# dozer_mover.net
KiCad netlist of a schematic drawn in EAGLE
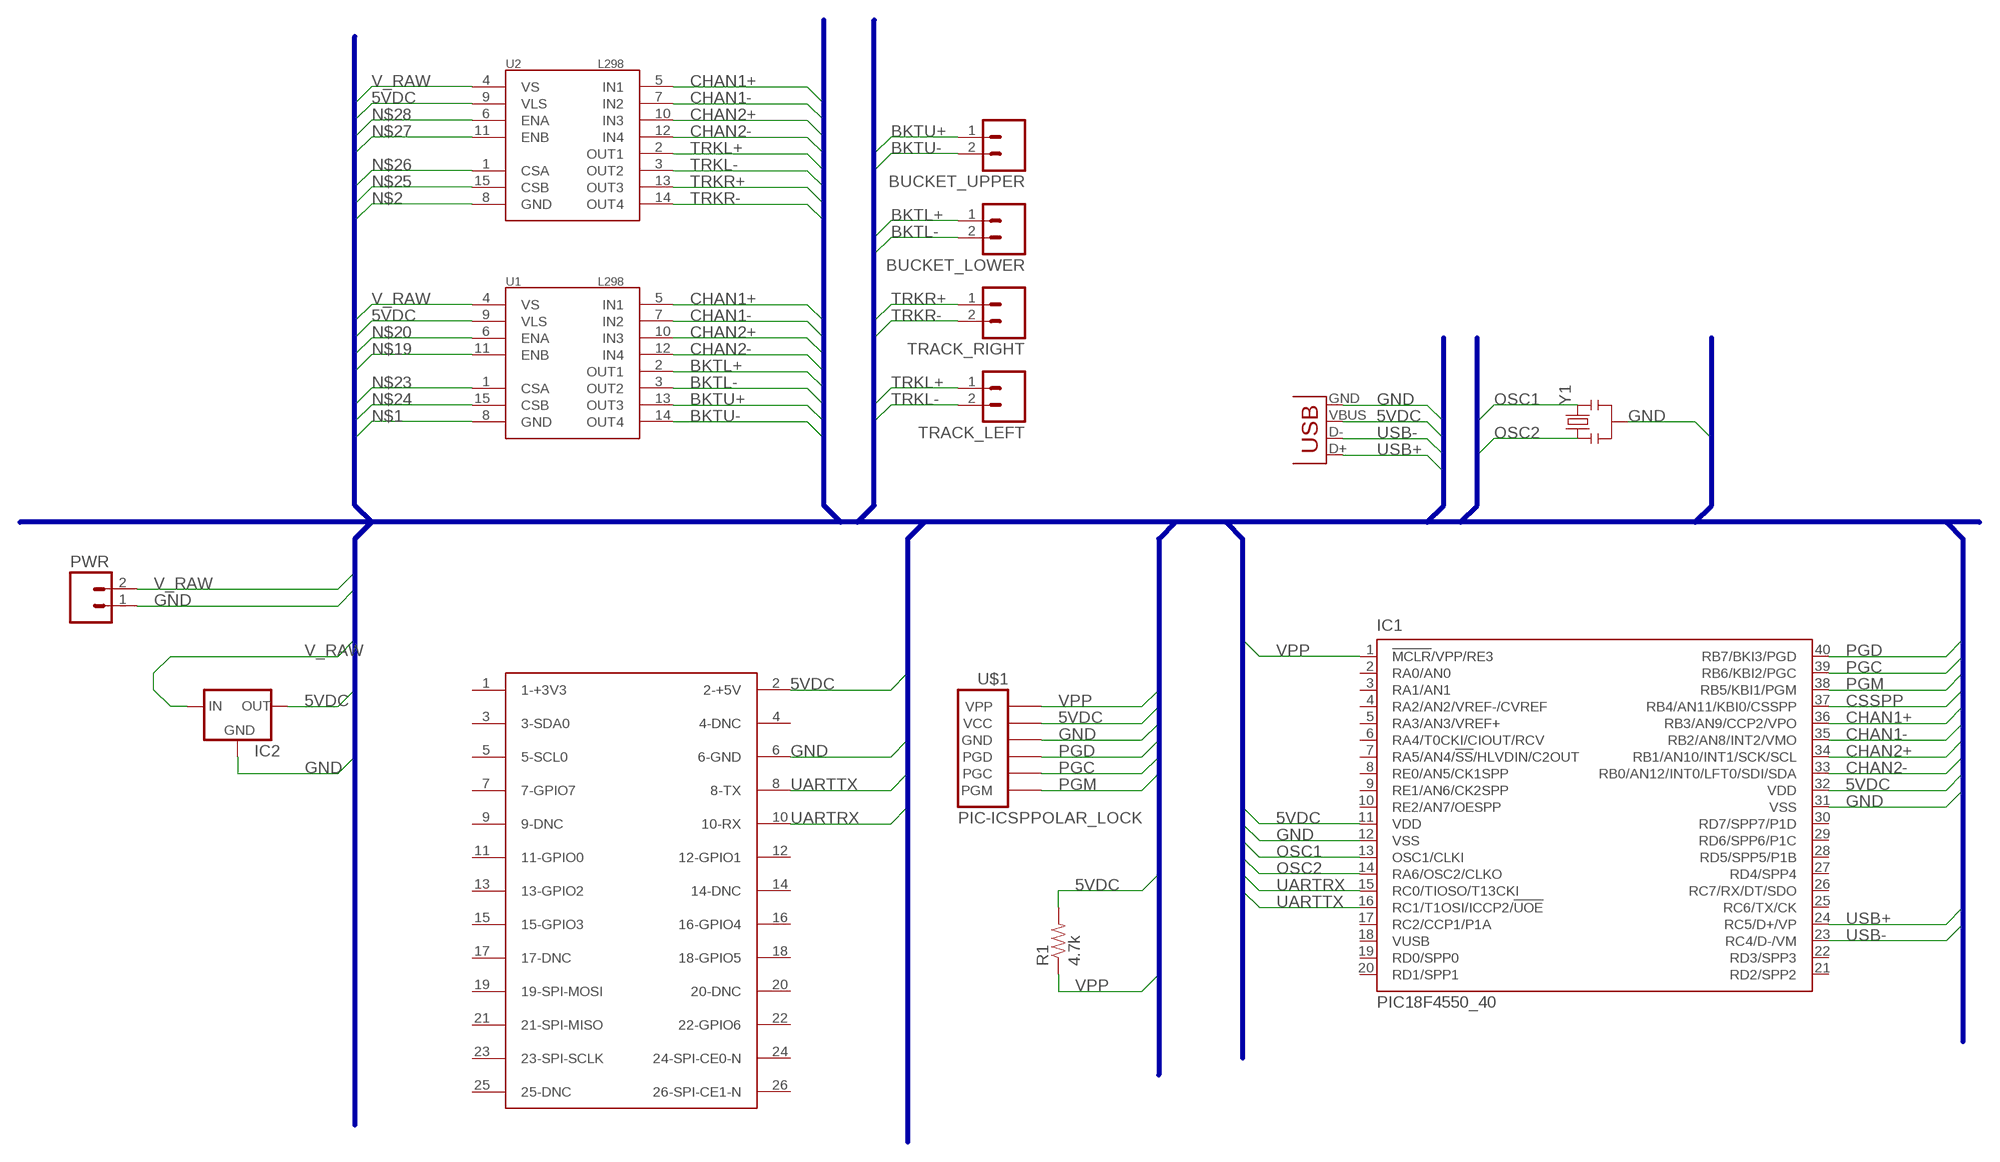
[diagram p0: schematic, sheet 1]

(export (version "E")
  (design (tool "Eeschema 10.0.6"))
  (components
    (comp (ref "BUCKET_LOWER")
      (value "M02JST-PTH-2")
      (footprint "eagle-import:JST-2-PTH")
      (libsource (lib "eagle-import") (part "M02JST-PTH-2"))
    )
    (comp (ref "BUCKET_UPPER")
      (value "M02JST-PTH-2")
      (footprint "eagle-import:JST-2-PTH")
      (libsource (lib "eagle-import") (part "M02JST-PTH-2"))
    )
    (comp (ref "IC1")
      (value "PIC18F4550_40")
      (footprint "eagle-import:DIL40")
      (fields (field (name "MF") "MICROCHIP") (field (name "MPN") "PIC18F4550-I/P"))
      (libsource (lib "eagle-import") (part "PIC18F4_40550"))
    )
    (comp (ref "IC2")
      (value "V_REG_78XXSINK")
      (footprint "eagle-import:TO220-IGO")
      (libsource (lib "eagle-import") (part "V_REG_78XXSINK"))
    )
    (comp (ref "J1")
      (value "RASPBERRY-PI")
      (footprint "eagle-import:RASPBERRY-PI")
      (libsource (lib "eagle-import") (part "RASPBERRY-PI"))
    )
    (comp (ref "JP1")
      (value "USB-MB-H")
      (footprint "eagle-import:USB-MB-H")
      (libsource (lib "eagle-import") (part "USB-MB-H"))
    )
    (comp (ref "PWR")
      (value "M02JST-PTH-2")
      (footprint "eagle-import:JST-2-PTH")
      (libsource (lib "eagle-import") (part "M02JST-PTH-2"))
    )
    (comp (ref "R1")
      (value "4.7k")
      (footprint "eagle-import:AXIAL-0.4")
      (libsource (lib "eagle-import") (part "RESISTORPTH-1/4W"))
    )
    (comp (ref "TRACK_LEFT")
      (value "M02JST-PTH-2")
      (footprint "eagle-import:JST-2-PTH")
      (libsource (lib "eagle-import") (part "M02JST-PTH-2"))
    )
    (comp (ref "TRACK_RIGHT")
      (value "M02JST-PTH-2")
      (footprint "eagle-import:JST-2-PTH")
      (libsource (lib "eagle-import") (part "M02JST-PTH-2"))
    )
    (comp (ref "U$1")
      (value "PIC-ICSPPOLAR_LOCK")
      (footprint "eagle-import:MOLEX-1X6_LOCK")
      (libsource (lib "eagle-import") (part "PIC-ICSPPOLAR_LOCK"))
    )
    (comp (ref "U1")
      (value "L298")
      (footprint "eagle-import:MULTIWATT15")
      (libsource (lib "eagle-import") (part "L298"))
    )
    (comp (ref "U2")
      (value "L298")
      (footprint "eagle-import:MULTIWATT15")
      (libsource (lib "eagle-import") (part "L298"))
    )
    (comp (ref "Y1")
      (value "RESONATORPTH")
      (footprint "eagle-import:RESONATOR-PTH")
      (libsource (lib "eagle-import") (part "RESONATORPTH"))
    )
  )
  (nets
    (net (code "1") (name "/5VDC") (class "Default")
      (node (ref "IC1") (pin "11") (pinfunction "VDD_11") (pintype "power_in"))
      (node (ref "IC1") (pin "32") (pinfunction "VDD_32") (pintype "power_in"))
      (node (ref "IC2") (pin "OUT") (pinfunction "OUT_OUT") (pintype "output"))
      (node (ref "J1") (pin "2") (pinfunction "2-+5V_2") (pintype "bidirectional"))
      (node (ref "JP1") (pin "VBUS") (pinfunction "VBUS_VBUS") (pintype "bidirectional"))
      (node (ref "R1") (pin "P$2") (pinfunction "2_P$2") (pintype "passive"))
      (node (ref "U$1") (pin "5") (pinfunction "VCC_5") (pintype "bidirectional"))
      (node (ref "U1") (pin "9") (pinfunction "VLS_9") (pintype "bidirectional"))
      (node (ref "U2") (pin "9") (pinfunction "VLS_9") (pintype "bidirectional"))
    )
    (net (code "2") (name "/BKTL+") (class "Default")
      (node (ref "BUCKET_LOWER") (pin "1") (pinfunction "1_1") (pintype "passive"))
      (node (ref "U1") (pin "2") (pinfunction "OUT1_2") (pintype "bidirectional"))
    )
    (net (code "3") (name "/BKTL-") (class "Default")
      (node (ref "BUCKET_LOWER") (pin "2") (pinfunction "2_2") (pintype "passive"))
      (node (ref "U1") (pin "3") (pinfunction "OUT2_3") (pintype "bidirectional"))
    )
    (net (code "4") (name "/BKTU+") (class "Default")
      (node (ref "BUCKET_UPPER") (pin "1") (pinfunction "1_1") (pintype "passive"))
      (node (ref "U1") (pin "13") (pinfunction "OUT3_13") (pintype "bidirectional"))
    )
    (net (code "5") (name "/BKTU-") (class "Default")
      (node (ref "BUCKET_UPPER") (pin "2") (pinfunction "2_2") (pintype "passive"))
      (node (ref "U1") (pin "14") (pinfunction "OUT4_14") (pintype "bidirectional"))
    )
    (net (code "6") (name "/CHAN1+") (class "Default")
      (node (ref "IC1") (pin "36") (pinfunction "RB3/AN9/CCP2/VPO_36") (pintype "bidirectional"))
      (node (ref "U1") (pin "5") (pinfunction "IN1_5") (pintype "bidirectional"))
      (node (ref "U2") (pin "5") (pinfunction "IN1_5") (pintype "bidirectional"))
    )
    (net (code "7") (name "/CHAN1-") (class "Default")
      (node (ref "IC1") (pin "35") (pinfunction "RB2/AN8/INT2/VMO_35") (pintype "bidirectional"))
      (node (ref "U1") (pin "7") (pinfunction "IN2_7") (pintype "bidirectional"))
      (node (ref "U2") (pin "7") (pinfunction "IN2_7") (pintype "bidirectional"))
    )
    (net (code "8") (name "/CHAN2+") (class "Default")
      (node (ref "IC1") (pin "34") (pinfunction "RB1/AN10/INT1/SCK/SCL_34") (pintype "bidirectional"))
      (node (ref "U1") (pin "10") (pinfunction "IN3_10") (pintype "bidirectional"))
      (node (ref "U2") (pin "10") (pinfunction "IN3_10") (pintype "bidirectional"))
    )
    (net (code "9") (name "/CHAN2-") (class "Default")
      (node (ref "IC1") (pin "33") (pinfunction "RB0/AN12/INT0/LFT0/SDI/SDA_33") (pintype "bidirectional"))
      (node (ref "U1") (pin "12") (pinfunction "IN4_12") (pintype "bidirectional"))
      (node (ref "U2") (pin "12") (pinfunction "IN4_12") (pintype "bidirectional"))
    )
    (net (code "10") (name "/CSSPP") (class "Default")
      (node (ref "IC1") (pin "37") (pinfunction "RB4/AN11/KBI0/CSSPP_37") (pintype "bidirectional"))
    )
    (net (code "11") (name "/GND") (class "Default")
      (node (ref "IC1") (pin "12") (pinfunction "VSS_12") (pintype "power_in"))
      (node (ref "IC1") (pin "31") (pinfunction "VSS_31") (pintype "power_in"))
      (node (ref "IC2") (pin "GND") (pinfunction "GND_GND") (pintype "input"))
      (node (ref "J1") (pin "6") (pinfunction "6-GND_6") (pintype "bidirectional"))
      (node (ref "JP1") (pin "GND") (pinfunction "GND_GND") (pintype "bidirectional"))
      (node (ref "PWR") (pin "1") (pinfunction "1_1") (pintype "passive"))
      (node (ref "U$1") (pin "4") (pinfunction "GND_4") (pintype "bidirectional"))
      (node (ref "Y1") (pin "2") (pinfunction "2_2") (pintype "passive"))
    )
    (net (code "12") (name "/N$1") (class "Default")
      (node (ref "U1") (pin "8") (pinfunction "GND_8") (pintype "bidirectional"))
    )
    (net (code "13") (name "/N$2") (class "Default")
      (node (ref "U2") (pin "8") (pinfunction "GND_8") (pintype "bidirectional"))
    )
    (net (code "14") (name "/N$19") (class "Default")
      (node (ref "U1") (pin "11") (pinfunction "ENB_11") (pintype "bidirectional"))
    )
    (net (code "15") (name "/N$20") (class "Default")
      (node (ref "U1") (pin "6") (pinfunction "ENA_6") (pintype "bidirectional"))
    )
    (net (code "16") (name "/N$23") (class "Default")
      (node (ref "U1") (pin "1") (pinfunction "CSA_1") (pintype "bidirectional"))
    )
    (net (code "17") (name "/N$24") (class "Default")
      (node (ref "U1") (pin "15") (pinfunction "CSB_15") (pintype "bidirectional"))
    )
    (net (code "18") (name "/N$25") (class "Default")
      (node (ref "U2") (pin "15") (pinfunction "CSB_15") (pintype "bidirectional"))
    )
    (net (code "19") (name "/N$26") (class "Default")
      (node (ref "U2") (pin "1") (pinfunction "CSA_1") (pintype "bidirectional"))
    )
    (net (code "20") (name "/N$27") (class "Default")
      (node (ref "U2") (pin "11") (pinfunction "ENB_11") (pintype "bidirectional"))
    )
    (net (code "21") (name "/N$28") (class "Default")
      (node (ref "U2") (pin "6") (pinfunction "ENA_6") (pintype "bidirectional"))
    )
    (net (code "22") (name "/OSC1") (class "Default")
      (node (ref "IC1") (pin "13") (pinfunction "OSC1/CLKI_13") (pintype "input"))
      (node (ref "Y1") (pin "3") (pinfunction "3_3") (pintype "passive"))
    )
    (net (code "23") (name "/OSC2") (class "Default")
      (node (ref "IC1") (pin "14") (pinfunction "RA6/OSC2/CLKO_14") (pintype "output"))
      (node (ref "Y1") (pin "1") (pinfunction "1_1") (pintype "passive"))
    )
    (net (code "24") (name "/PGC") (class "Default")
      (node (ref "IC1") (pin "39") (pinfunction "RB6/KBI2/PGC_39") (pintype "bidirectional"))
      (node (ref "U$1") (pin "2") (pinfunction "PGC_2") (pintype "bidirectional"))
    )
    (net (code "25") (name "/PGD") (class "Default")
      (node (ref "IC1") (pin "40") (pinfunction "RB7/BKI3/PGD_40") (pintype "bidirectional"))
      (node (ref "U$1") (pin "3") (pinfunction "PGD_3") (pintype "bidirectional"))
    )
    (net (code "26") (name "/PGM") (class "Default")
      (node (ref "IC1") (pin "38") (pinfunction "RB5/KBI1/PGM_38") (pintype "bidirectional"))
      (node (ref "U$1") (pin "1") (pinfunction "PGM_1") (pintype "bidirectional"))
    )
    (net (code "27") (name "/TRKL+") (class "Default")
      (node (ref "TRACK_LEFT") (pin "1") (pinfunction "1_1") (pintype "passive"))
      (node (ref "U2") (pin "2") (pinfunction "OUT1_2") (pintype "bidirectional"))
    )
    (net (code "28") (name "/TRKL-") (class "Default")
      (node (ref "TRACK_LEFT") (pin "2") (pinfunction "2_2") (pintype "passive"))
      (node (ref "U2") (pin "3") (pinfunction "OUT2_3") (pintype "bidirectional"))
    )
    (net (code "29") (name "/TRKR+") (class "Default")
      (node (ref "TRACK_RIGHT") (pin "1") (pinfunction "1_1") (pintype "passive"))
      (node (ref "U2") (pin "13") (pinfunction "OUT3_13") (pintype "bidirectional"))
    )
    (net (code "30") (name "/TRKR-") (class "Default")
      (node (ref "TRACK_RIGHT") (pin "2") (pinfunction "2_2") (pintype "passive"))
      (node (ref "U2") (pin "14") (pinfunction "OUT4_14") (pintype "bidirectional"))
    )
    (net (code "31") (name "/UARTRX") (class "Default")
      (node (ref "IC1") (pin "15") (pinfunction "RC0/TIOSO/T13CKI_15") (pintype "bidirectional"))
      (node (ref "J1") (pin "10") (pinfunction "10-RX_10") (pintype "bidirectional"))
    )
    (net (code "32") (name "/UARTTX") (class "Default")
      (node (ref "IC1") (pin "16") (pinfunction "RC1/T1OSI/ICCP2/~{UOE}_16") (pintype "bidirectional"))
      (node (ref "J1") (pin "8") (pinfunction "8-TX_8") (pintype "bidirectional"))
    )
    (net (code "33") (name "/USB+") (class "Default")
      (node (ref "IC1") (pin "24") (pinfunction "RC5/D+/VP_24") (pintype "bidirectional"))
      (node (ref "JP1") (pin "D+") (pinfunction "D+_D+") (pintype "bidirectional"))
    )
    (net (code "34") (name "/USB-") (class "Default")
      (node (ref "IC1") (pin "23") (pinfunction "RC4/D-/VM_23") (pintype "bidirectional"))
      (node (ref "JP1") (pin "D-") (pinfunction "D-_D-") (pintype "bidirectional"))
    )
    (net (code "35") (name "/VPP") (class "Default")
      (node (ref "IC1") (pin "1") (pinfunction "~{MCLR}/VPP/RE3_1") (pintype "input"))
      (node (ref "R1") (pin "P$1") (pinfunction "1_P$1") (pintype "passive"))
      (node (ref "U$1") (pin "6") (pinfunction "VPP_6") (pintype "bidirectional"))
    )
    (net (code "36") (name "/V_RAW") (class "Default")
      (node (ref "IC2") (pin "IN") (pinfunction "IN_IN") (pintype "input"))
      (node (ref "PWR") (pin "2") (pinfunction "2_2") (pintype "passive"))
      (node (ref "U1") (pin "4") (pinfunction "VS_4") (pintype "bidirectional"))
      (node (ref "U2") (pin "4") (pinfunction "VS_4") (pintype "bidirectional"))
    )
    (net (code "37") (name "unconnected-(IC1-RA0{slash}AN0-Pad2)") (class "Default")
      (node (ref "IC1") (pin "2") (pinfunction "RA0/AN0_2") (pintype "bidirectional"))
    )
    (net (code "38") (name "unconnected-(IC1-RA1{slash}AN1-Pad3)") (class "Default")
      (node (ref "IC1") (pin "3") (pinfunction "RA1/AN1_3") (pintype "bidirectional"))
    )
    (net (code "39") (name "unconnected-(IC1-RA2{slash}AN2{slash}VREF-{slash}CVREF-Pad4)") (class "Default")
      (node (ref "IC1") (pin "4") (pinfunction "RA2/AN2/VREF-/CVREF_4") (pintype "bidirectional"))
    )
    (net (code "40") (name "unconnected-(IC1-RA3{slash}AN3{slash}VREF+-Pad5)") (class "Default")
      (node (ref "IC1") (pin "5") (pinfunction "RA3/AN3/VREF+_5") (pintype "bidirectional"))
    )
    (net (code "41") (name "unconnected-(IC1-RA4{slash}T0CKI{slash}CIOUT{slash}RCV-Pad6)") (class "Default")
      (node (ref "IC1") (pin "6") (pinfunction "RA4/T0CKI/CIOUT/RCV_6") (pintype "bidirectional"))
    )
    (net (code "42") (name "unconnected-(IC1-RA5{slash}AN4{slash}~{SS}{slash}HLVDIN{slash}C2OUT-Pad7)") (class "Default")
      (node (ref "IC1") (pin "7") (pinfunction "RA5/AN4/~{SS}/HLVDIN/C2OUT_7") (pintype "bidirectional"))
    )
    (net (code "43") (name "unconnected-(IC1-RC2{slash}CCP1{slash}P1A-Pad17)") (class "Default")
      (node (ref "IC1") (pin "17") (pinfunction "RC2/CCP1/P1A_17") (pintype "bidirectional"))
    )
    (net (code "44") (name "unconnected-(IC1-RC6{slash}TX{slash}CK-Pad25)") (class "Default")
      (node (ref "IC1") (pin "25") (pinfunction "RC6/TX/CK_25") (pintype "bidirectional"))
    )
    (net (code "45") (name "unconnected-(IC1-RC7{slash}RX{slash}DT{slash}SDO-Pad26)") (class "Default")
      (node (ref "IC1") (pin "26") (pinfunction "RC7/RX/DT/SDO_26") (pintype "bidirectional"))
    )
    (net (code "46") (name "unconnected-(IC1-RD0{slash}SPP0-Pad19)") (class "Default")
      (node (ref "IC1") (pin "19") (pinfunction "RD0/SPP0_19") (pintype "bidirectional"))
    )
    (net (code "47") (name "unconnected-(IC1-RD1{slash}SPP1-Pad20)") (class "Default")
      (node (ref "IC1") (pin "20") (pinfunction "RD1/SPP1_20") (pintype "bidirectional"))
    )
    (net (code "48") (name "unconnected-(IC1-RD2{slash}SPP2-Pad21)") (class "Default")
      (node (ref "IC1") (pin "21") (pinfunction "RD2/SPP2_21") (pintype "bidirectional"))
    )
    (net (code "49") (name "unconnected-(IC1-RD3{slash}SPP3-Pad22)") (class "Default")
      (node (ref "IC1") (pin "22") (pinfunction "RD3/SPP3_22") (pintype "bidirectional"))
    )
    (net (code "50") (name "unconnected-(IC1-RD4{slash}SPP4-Pad27)") (class "Default")
      (node (ref "IC1") (pin "27") (pinfunction "RD4/SPP4_27") (pintype "bidirectional"))
    )
    (net (code "51") (name "unconnected-(IC1-RD5{slash}SPP5{slash}P1B-Pad28)") (class "Default")
      (node (ref "IC1") (pin "28") (pinfunction "RD5/SPP5/P1B_28") (pintype "bidirectional"))
    )
    (net (code "52") (name "unconnected-(IC1-RD6{slash}SPP6{slash}P1C-Pad29)") (class "Default")
      (node (ref "IC1") (pin "29") (pinfunction "RD6/SPP6/P1C_29") (pintype "bidirectional"))
    )
    (net (code "53") (name "unconnected-(IC1-RD7{slash}SPP7{slash}P1D-Pad30)") (class "Default")
      (node (ref "IC1") (pin "30") (pinfunction "RD7/SPP7/P1D_30") (pintype "bidirectional"))
    )
    (net (code "54") (name "unconnected-(IC1-RE0{slash}AN5{slash}CK1SPP-Pad8)") (class "Default")
      (node (ref "IC1") (pin "8") (pinfunction "RE0/AN5/CK1SPP_8") (pintype "bidirectional"))
    )
    (net (code "55") (name "unconnected-(IC1-RE1{slash}AN6{slash}CK2SPP-Pad9)") (class "Default")
      (node (ref "IC1") (pin "9") (pinfunction "RE1/AN6/CK2SPP_9") (pintype "bidirectional"))
    )
    (net (code "56") (name "unconnected-(IC1-RE2{slash}AN7{slash}OESPP-Pad10)") (class "Default")
      (node (ref "IC1") (pin "10") (pinfunction "RE2/AN7/OESPP_10") (pintype "bidirectional"))
    )
    (net (code "57") (name "unconnected-(IC1-VUSB-Pad18)") (class "Default")
      (node (ref "IC1") (pin "18") (pinfunction "VUSB_18") (pintype "bidirectional"))
    )
    (net (code "58") (name "unconnected-(J1-1-+3V3-Pad1)") (class "Default")
      (node (ref "J1") (pin "1") (pinfunction "1-+3V3_1") (pintype "bidirectional"))
    )
    (net (code "59") (name "unconnected-(J1-3-SDA0-Pad3)") (class "Default")
      (node (ref "J1") (pin "3") (pinfunction "3-SDA0_3") (pintype "bidirectional"))
    )
    (net (code "60") (name "unconnected-(J1-4-DNC-Pad4)") (class "Default")
      (node (ref "J1") (pin "4") (pinfunction "4-DNC_4") (pintype "bidirectional"))
    )
    (net (code "61") (name "unconnected-(J1-5-SCL0-Pad5)") (class "Default")
      (node (ref "J1") (pin "5") (pinfunction "5-SCL0_5") (pintype "bidirectional"))
    )
    (net (code "62") (name "unconnected-(J1-7-GPIO7-Pad7)") (class "Default")
      (node (ref "J1") (pin "7") (pinfunction "7-GPIO7_7") (pintype "bidirectional"))
    )
    (net (code "63") (name "unconnected-(J1-9-DNC-Pad9)") (class "Default")
      (node (ref "J1") (pin "9") (pinfunction "9-DNC_9") (pintype "bidirectional"))
    )
    (net (code "64") (name "unconnected-(J1-11-GPIO0-Pad11)") (class "Default")
      (node (ref "J1") (pin "11") (pinfunction "11-GPIO0_11") (pintype "bidirectional"))
    )
    (net (code "65") (name "unconnected-(J1-12-GPIO1-Pad12)") (class "Default")
      (node (ref "J1") (pin "12") (pinfunction "12-GPIO1_12") (pintype "bidirectional"))
    )
    (net (code "66") (name "unconnected-(J1-13-GPIO2-Pad13)") (class "Default")
      (node (ref "J1") (pin "13") (pinfunction "13-GPIO2_13") (pintype "bidirectional"))
    )
    (net (code "67") (name "unconnected-(J1-14-DNC-Pad14)") (class "Default")
      (node (ref "J1") (pin "14") (pinfunction "14-DNC_14") (pintype "bidirectional"))
    )
    (net (code "68") (name "unconnected-(J1-15-GPIO3-Pad15)") (class "Default")
      (node (ref "J1") (pin "15") (pinfunction "15-GPIO3_15") (pintype "bidirectional"))
    )
    (net (code "69") (name "unconnected-(J1-16-GPIO4-Pad16)") (class "Default")
      (node (ref "J1") (pin "16") (pinfunction "16-GPIO4_16") (pintype "bidirectional"))
    )
    (net (code "70") (name "unconnected-(J1-17-DNC-Pad17)") (class "Default")
      (node (ref "J1") (pin "17") (pinfunction "17-DNC_17") (pintype "bidirectional"))
    )
    (net (code "71") (name "unconnected-(J1-18-GPIO5-Pad18)") (class "Default")
      (node (ref "J1") (pin "18") (pinfunction "18-GPIO5_18") (pintype "bidirectional"))
    )
    (net (code "72") (name "unconnected-(J1-19-SPI-MOSI-Pad19)") (class "Default")
      (node (ref "J1") (pin "19") (pinfunction "19-SPI-MOSI_19") (pintype "bidirectional"))
    )
    (net (code "73") (name "unconnected-(J1-20-DNC-Pad20)") (class "Default")
      (node (ref "J1") (pin "20") (pinfunction "20-DNC_20") (pintype "bidirectional"))
    )
    (net (code "74") (name "unconnected-(J1-21-SPI-MISO-Pad21)") (class "Default")
      (node (ref "J1") (pin "21") (pinfunction "21-SPI-MISO_21") (pintype "bidirectional"))
    )
    (net (code "75") (name "unconnected-(J1-22-GPIO6-Pad22)") (class "Default")
      (node (ref "J1") (pin "22") (pinfunction "22-GPIO6_22") (pintype "bidirectional"))
    )
    (net (code "76") (name "unconnected-(J1-23-SPI-SCLK-Pad23)") (class "Default")
      (node (ref "J1") (pin "23") (pinfunction "23-SPI-SCLK_23") (pintype "bidirectional"))
    )
    (net (code "77") (name "unconnected-(J1-24-SPI-CE0-N-Pad24)") (class "Default")
      (node (ref "J1") (pin "24") (pinfunction "24-SPI-CE0-N_24") (pintype "bidirectional"))
    )
    (net (code "78") (name "unconnected-(J1-25-DNC-Pad25)") (class "Default")
      (node (ref "J1") (pin "25") (pinfunction "25-DNC_25") (pintype "bidirectional"))
    )
    (net (code "79") (name "unconnected-(J1-26-SPI-CE1-N-Pad26)") (class "Default")
      (node (ref "J1") (pin "26") (pinfunction "26-SPI-CE1-N_26") (pintype "bidirectional"))
    )
  )
)
